# Button3x4S-1_Sch.net
KiCad netlist of a schematic drawn in Altium Designer
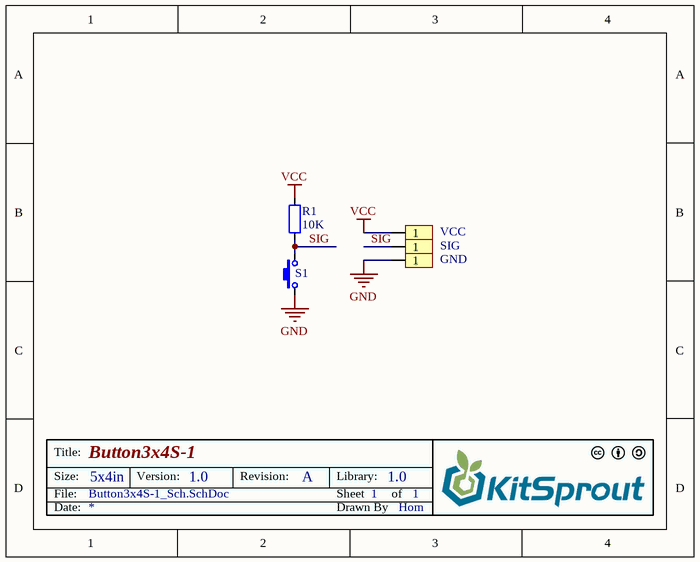
[diagram p0: Button3x4S-1_Sch.SchDoc]

(export (version "E")
  (design (tool "Eeschema 10.0.6"))
  (components
    (comp (ref "GND")
      (value "HDR-PAD_2.54")
      (footprint "PCB_ConnectorHDR:HDR-PAD_2.54")
      (description "Header")
      (libsource (lib "SCH_ConnectorHDR") (part "HDR-PAD_2.54"))
    )
    (comp (ref "R1")
      (value "10K")
      (footprint "PCB_PassiveRes:RES_0603")
      (description "Resistor")
      (fields (field (name "Comment") "Res_0603"))
      (libsource (lib "SCH_Passive") (part "Res_0603"))
    )
    (comp (ref "S1")
      (value "ButtonTACT_3x4x2_180")
      (footprint "PCB_Switch:ButtonTACT_3x4x2_180H")
      (description "Button")
      (libsource (lib "SCH_Switch") (part "ButtonTACT_3x4x2_180"))
    )
    (comp (ref "SIG")
      (value "HDR-PAD_2.54")
      (footprint "PCB_ConnectorHDR:HDR-PAD_2.54")
      (description "Header")
      (libsource (lib "SCH_ConnectorHDR") (part "HDR-PAD_2.54"))
    )
    (comp (ref "VCC")
      (value "HDR-PAD_2.54")
      (footprint "PCB_ConnectorHDR:HDR-PAD_2.54")
      (description "Header")
      (libsource (lib "SCH_ConnectorHDR") (part "HDR-PAD_2.54"))
    )
  )
  (nets
    (net (code "1") (name "/SIG") (class "Default")
      (node (ref "R1") (pin "1") (pinfunction "1_1") (pintype "passive"))
      (node (ref "S1") (pin "2") (pinfunction "2_2") (pintype "passive"))
      (node (ref "SIG") (pin "1") (pinfunction "1_1") (pintype "passive"))
    )
    (net (code "2") (name "GND") (class "Default")
      (node (ref "GND") (pin "1") (pinfunction "1_1") (pintype "passive"))
      (node (ref "S1") (pin "1") (pinfunction "1_1") (pintype "passive"))
    )
    (net (code "3") (name "VCC") (class "Default")
      (node (ref "R1") (pin "2") (pinfunction "2_2") (pintype "passive"))
      (node (ref "VCC") (pin "1") (pinfunction "1_1") (pintype "passive"))
    )
  )
)
